# led_driver.net
KiCad netlist of a schematic drawn in Altium Designer
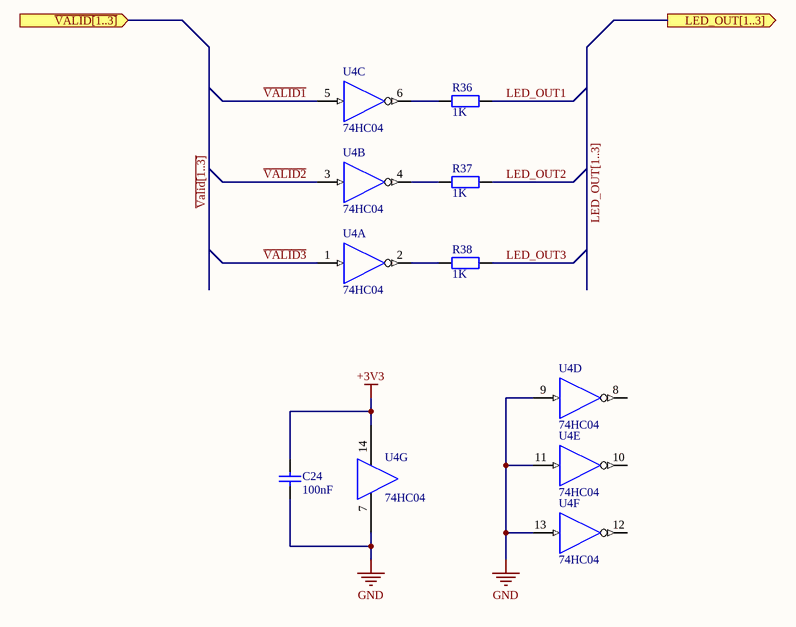
[diagram p0: led_driver.SchDoc]

(export (version "E")
  (design (tool "Eeschema 10.0.6"))
  (components
    (comp (ref "C24")
      (value "100nF")
      (footprint "C2012")
      (description "Capacitor")
      (fields (field (name "PUBLISHER") "Altium Limited"))
      (libsource (lib "Miscellaneous Devices") (part "Cap"))
    )
    (comp (ref "R36")
      (value "1K")
      (footprint "R2012")
      (description "Resistor")
      (fields (field (name "PUBLISHER") "Altium Limited"))
      (libsource (lib "Miscellaneous Devices") (part "Res2"))
    )
    (comp (ref "R37")
      (value "1K")
      (footprint "R2012")
      (description "Resistor")
      (fields (field (name "PUBLISHER") "Altium Limited"))
      (libsource (lib "Miscellaneous Devices") (part "Res2"))
    )
    (comp (ref "R38")
      (value "1K")
      (footprint "R2012")
      (description "Resistor")
      (fields (field (name "PUBLISHER") "Altium Limited"))
      (libsource (lib "Miscellaneous Devices") (part "Res2"))
    )
    (comp (ref "U4")
      (value "74HC04")
      (footprint "SOIC14")
      (description "Hex Inverter")
      (libsource (lib "bitbots") (part "74HC04"))
    )
  )
  (nets
    (net (code "4") (name "+3V3") (class "Default")
      (node (ref "C24") (pin "2") (pinfunction "2_2") (pintype "passive"))
      (node (ref "U4") (pin "14") (pinfunction "VCC_14") (pintype "power_in"))
    )
    (net (code "5") (name "/LED_OUT1") (class "Default")
      (node (ref "R36") (pin "2") (pinfunction "2_2") (pintype "passive"))
    )
    (net (code "6") (name "/LED_OUT2") (class "Default")
      (node (ref "R37") (pin "2") (pinfunction "2_2") (pintype "passive"))
    )
    (net (code "7") (name "/LED_OUT3") (class "Default")
      (node (ref "R38") (pin "2") (pinfunction "2_2") (pintype "passive"))
    )
    (net (code "9") (name "/Valid1") (class "Default")
      (node (ref "U4") (pin "5") (pinfunction "A_5") (pintype "input"))
    )
    (net (code "10") (name "/Valid2") (class "Default")
      (node (ref "U4") (pin "3") (pinfunction "A_3") (pintype "input"))
    )
    (net (code "11") (name "/Valid3") (class "Default")
      (node (ref "U4") (pin "1") (pinfunction "A_1") (pintype "input"))
    )
    (net (code "13") (name "GND") (class "Default")
      (node (ref "C24") (pin "1") (pinfunction "1_1") (pintype "passive"))
      (node (ref "U4") (pin "11") (pinfunction "A_11") (pintype "input"))
      (node (ref "U4") (pin "13") (pinfunction "A_13") (pintype "input"))
      (node (ref "U4") (pin "7") (pinfunction "GND_7") (pintype "power_in"))
      (node (ref "U4") (pin "9") (pinfunction "A_9") (pintype "input"))
    )
    (net (code "14") (name "Net-(U4A-Y)") (class "Default")
      (node (ref "R38") (pin "1") (pinfunction "1_1") (pintype "passive"))
      (node (ref "U4") (pin "2") (pinfunction "Y_2") (pintype "output"))
    )
    (net (code "15") (name "Net-(U4B-Y)") (class "Default")
      (node (ref "R37") (pin "1") (pinfunction "1_1") (pintype "passive"))
      (node (ref "U4") (pin "4") (pinfunction "Y_4") (pintype "output"))
    )
    (net (code "16") (name "Net-(U4C-Y)") (class "Default")
      (node (ref "R36") (pin "1") (pinfunction "1_1") (pintype "passive"))
      (node (ref "U4") (pin "6") (pinfunction "Y_6") (pintype "output"))
    )
    (net (code "17") (name "unconnected-(U4D-Y-Pad8)") (class "Default")
      (node (ref "U4") (pin "8") (pinfunction "Y_8") (pintype "output"))
    )
    (net (code "18") (name "unconnected-(U4E-Y-Pad10)") (class "Default")
      (node (ref "U4") (pin "10") (pinfunction "Y_10") (pintype "output"))
    )
    (net (code "19") (name "unconnected-(U4F-Y-Pad12)") (class "Default")
      (node (ref "U4") (pin "12") (pinfunction "Y_12") (pintype "output"))
    )
  )
)
